# BatteryCharger_I2C_V1.net
KiCad netlist of a schematic drawn in EAGLE
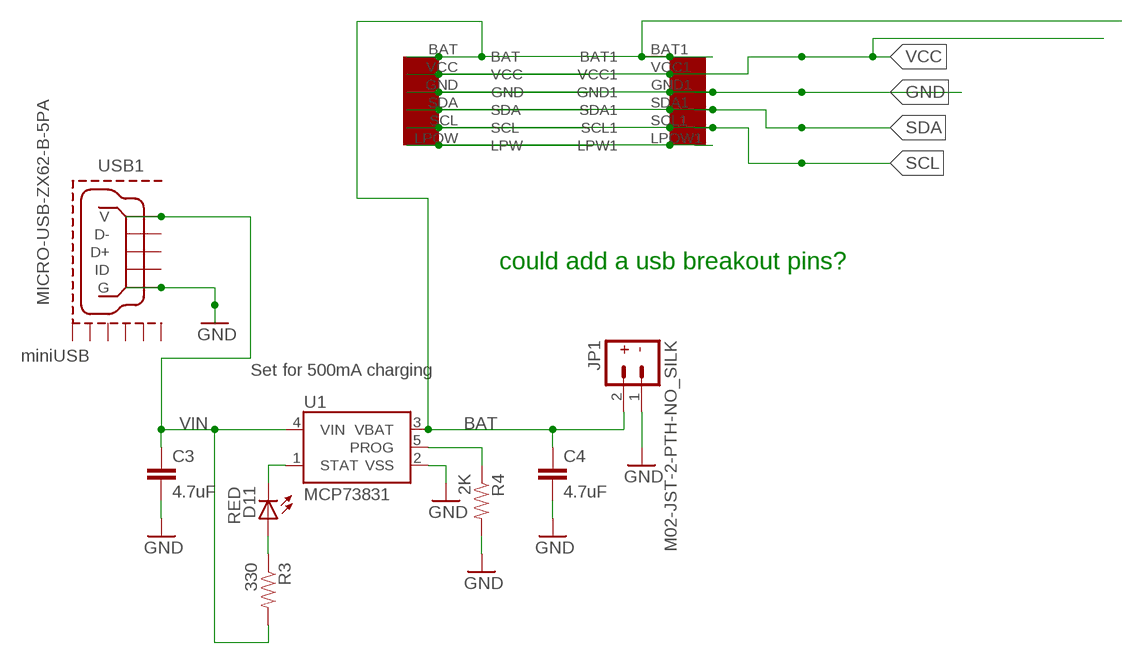
[diagram p0: schematic, sheet 1]

(export (version "E")
  (design (tool "Eeschema 10.0.6"))
  (components
    (comp (ref "C3")
      (value "4.7uF")
      (footprint "eagle-import:0402-CAP")
      (libsource (lib "eagle-import") (part "CAP0402-CAP"))
    )
    (comp (ref "C4")
      (value "4.7uF")
      (footprint "eagle-import:0402-CAP")
      (libsource (lib "eagle-import") (part "CAP0402-CAP"))
    )
    (comp (ref "D11")
      (value "RED")
      (footprint "eagle-import:LED-0603")
      (libsource (lib "eagle-import") (part "LED0603"))
    )
    (comp (ref "JP1")
      (value "M02-JST-2-PTH-NO_SILK")
      (footprint "eagle-import:JST-2-PTH-NS")
      (libsource (lib "eagle-import") (part "M02-JST-2-PTH-NO_SILK"))
    )
    (comp (ref "R3")
      (value "330")
      (footprint "eagle-import:0402-RES")
      (libsource (lib "eagle-import") (part "RESISTOR0402-RES"))
    )
    (comp (ref "R4")
      (value "2K")
      (footprint "eagle-import:0402-RES")
      (libsource (lib "eagle-import") (part "RESISTOR0402-RES"))
    )
    (comp (ref "U$1")
      (value "EZ-I2CHEADERV1")
      (footprint "eagle-import:EZ-I2CHEADERV1")
      (libsource (lib "eagle-import") (part "EZ-I2CHEADERV1"))
    )
    (comp (ref "U1")
      (value "MCP73831")
      (footprint "eagle-import:SOT23-5")
      (libsource (lib "eagle-import") (part "MCP73831"))
    )
    (comp (ref "USB1")
      (value "MICRO-USB-ZX62-B-5PA")
      (footprint "eagle-import:ZX62-B-5PA")
      (libsource (lib "eagle-import") (part "MICRO-USB-ZX62-B-5PA"))
    )
  )
  (nets
    (net (code "1") (name "/BAT") (class "Default")
      (node (ref "C4") (pin "1") (pinfunction "1_1") (pintype "passive"))
      (node (ref "JP1") (pin "2") (pinfunction "2_2") (pintype "passive"))
      (node (ref "U$1") (pin "BAT") (pinfunction "BAT_BAT") (pintype "bidirectional"))
      (node (ref "U$1") (pin "BAT1") (pinfunction "BAT1_BAT1") (pintype "bidirectional"))
      (node (ref "U1") (pin "3") (pinfunction "VBAT_3") (pintype "power_in"))
    )
    (net (code "2") (name "/GND1") (class "Default")
      (node (ref "USB1") (pin "GND@1") (pinfunction "GND1_GND@1") (pintype "power_in"))
    )
    (net (code "3") (name "/GND2") (class "Default")
      (node (ref "USB1") (pin "GND@2") (pinfunction "GND2_GND@2") (pintype "power_in"))
    )
    (net (code "4") (name "/GND3") (class "Default")
      (node (ref "USB1") (pin "GND@3") (pinfunction "GND3_GND@3") (pintype "power_in"))
    )
    (net (code "5") (name "/GND4") (class "Default")
      (node (ref "USB1") (pin "GND@4") (pinfunction "GND4_GND@4") (pintype "power_in"))
    )
    (net (code "6") (name "/GND5") (class "Default")
      (node (ref "USB1") (pin "GND@5") (pinfunction "GND5_GND@5") (pintype "power_in"))
    )
    (net (code "7") (name "/GND6") (class "Default")
      (node (ref "USB1") (pin "GND@6") (pinfunction "GND6_GND@6") (pintype "power_in"))
    )
    (net (code "8") (name "/VIN") (class "Default")
      (node (ref "C3") (pin "1") (pinfunction "1_1") (pintype "passive"))
      (node (ref "R3") (pin "2") (pinfunction "2_2") (pintype "passive"))
      (node (ref "U1") (pin "4") (pinfunction "VIN_4") (pintype "power_in"))
      (node (ref "USB1") (pin "1") (pinfunction "V_1") (pintype "input"))
    )
    (net (code "9") (name "GND") (class "Default")
      (node (ref "C3") (pin "2") (pinfunction "2_2") (pintype "passive"))
      (node (ref "C4") (pin "2") (pinfunction "2_2") (pintype "passive"))
      (node (ref "JP1") (pin "1") (pinfunction "1_1") (pintype "passive"))
      (node (ref "R4") (pin "2") (pinfunction "2_2") (pintype "passive"))
      (node (ref "U$1") (pin "GND") (pinfunction "GND_GND") (pintype "bidirectional"))
      (node (ref "U$1") (pin "GND1") (pinfunction "GND1_GND1") (pintype "bidirectional"))
      (node (ref "U1") (pin "2") (pinfunction "VSS_2") (pintype "power_in"))
      (node (ref "USB1") (pin "5") (pinfunction "G_5") (pintype "input"))
    )
    (net (code "10") (name "Net-(D11-PadA)") (class "Default")
      (node (ref "D11") (pin "A") (pinfunction "A_A") (pintype "passive"))
      (node (ref "R3") (pin "1") (pinfunction "1_1") (pintype "passive"))
    )
    (net (code "11") (name "Net-(U$1-LPW)") (class "Default")
      (node (ref "U$1") (pin "LPOW") (pinfunction "LPW_LPOW") (pintype "bidirectional"))
      (node (ref "U$1") (pin "LPOW1") (pinfunction "LPW1_LPOW1") (pintype "bidirectional"))
    )
    (net (code "12") (name "Net-(U1-PROG)") (class "Default")
      (node (ref "R4") (pin "1") (pinfunction "1_1") (pintype "passive"))
      (node (ref "U1") (pin "5") (pinfunction "PROG_5") (pintype "input"))
    )
    (net (code "13") (name "Net-(U1-STAT)") (class "Default")
      (node (ref "D11") (pin "C") (pinfunction "C_C") (pintype "passive"))
      (node (ref "U1") (pin "1") (pinfunction "STAT_1") (pintype "output"))
    )
    (net (code "14") (name "SCL") (class "Default")
      (node (ref "U$1") (pin "SCL") (pinfunction "SCL_SCL") (pintype "bidirectional"))
      (node (ref "U$1") (pin "SCL1") (pinfunction "SCL1_SCL1") (pintype "bidirectional"))
    )
    (net (code "15") (name "SDA") (class "Default")
      (node (ref "U$1") (pin "SDA") (pinfunction "SDA_SDA") (pintype "bidirectional"))
      (node (ref "U$1") (pin "SDA1") (pinfunction "SDA1_SDA1") (pintype "bidirectional"))
    )
    (net (code "16") (name "VCC") (class "Default")
      (node (ref "U$1") (pin "VCC") (pinfunction "VCC_VCC") (pintype "bidirectional"))
      (node (ref "U$1") (pin "VCC1") (pinfunction "VCC1_VCC1") (pintype "bidirectional"))
    )
    (net (code "17") (name "unconnected-(USB1-D+-Pad3)") (class "Default")
      (node (ref "USB1") (pin "3") (pinfunction "D+_3") (pintype "input"))
    )
    (net (code "18") (name "unconnected-(USB1-D--Pad2)") (class "Default")
      (node (ref "USB1") (pin "2") (pinfunction "D-_2") (pintype "input"))
    )
    (net (code "19") (name "unconnected-(USB1-ID-Pad4)") (class "Default")
      (node (ref "USB1") (pin "4") (pinfunction "ID_4") (pintype "input"))
    )
  )
)
